# pmod_clock_961c7fa4.net
KiCad netlist of a schematic drawn in EAGLE
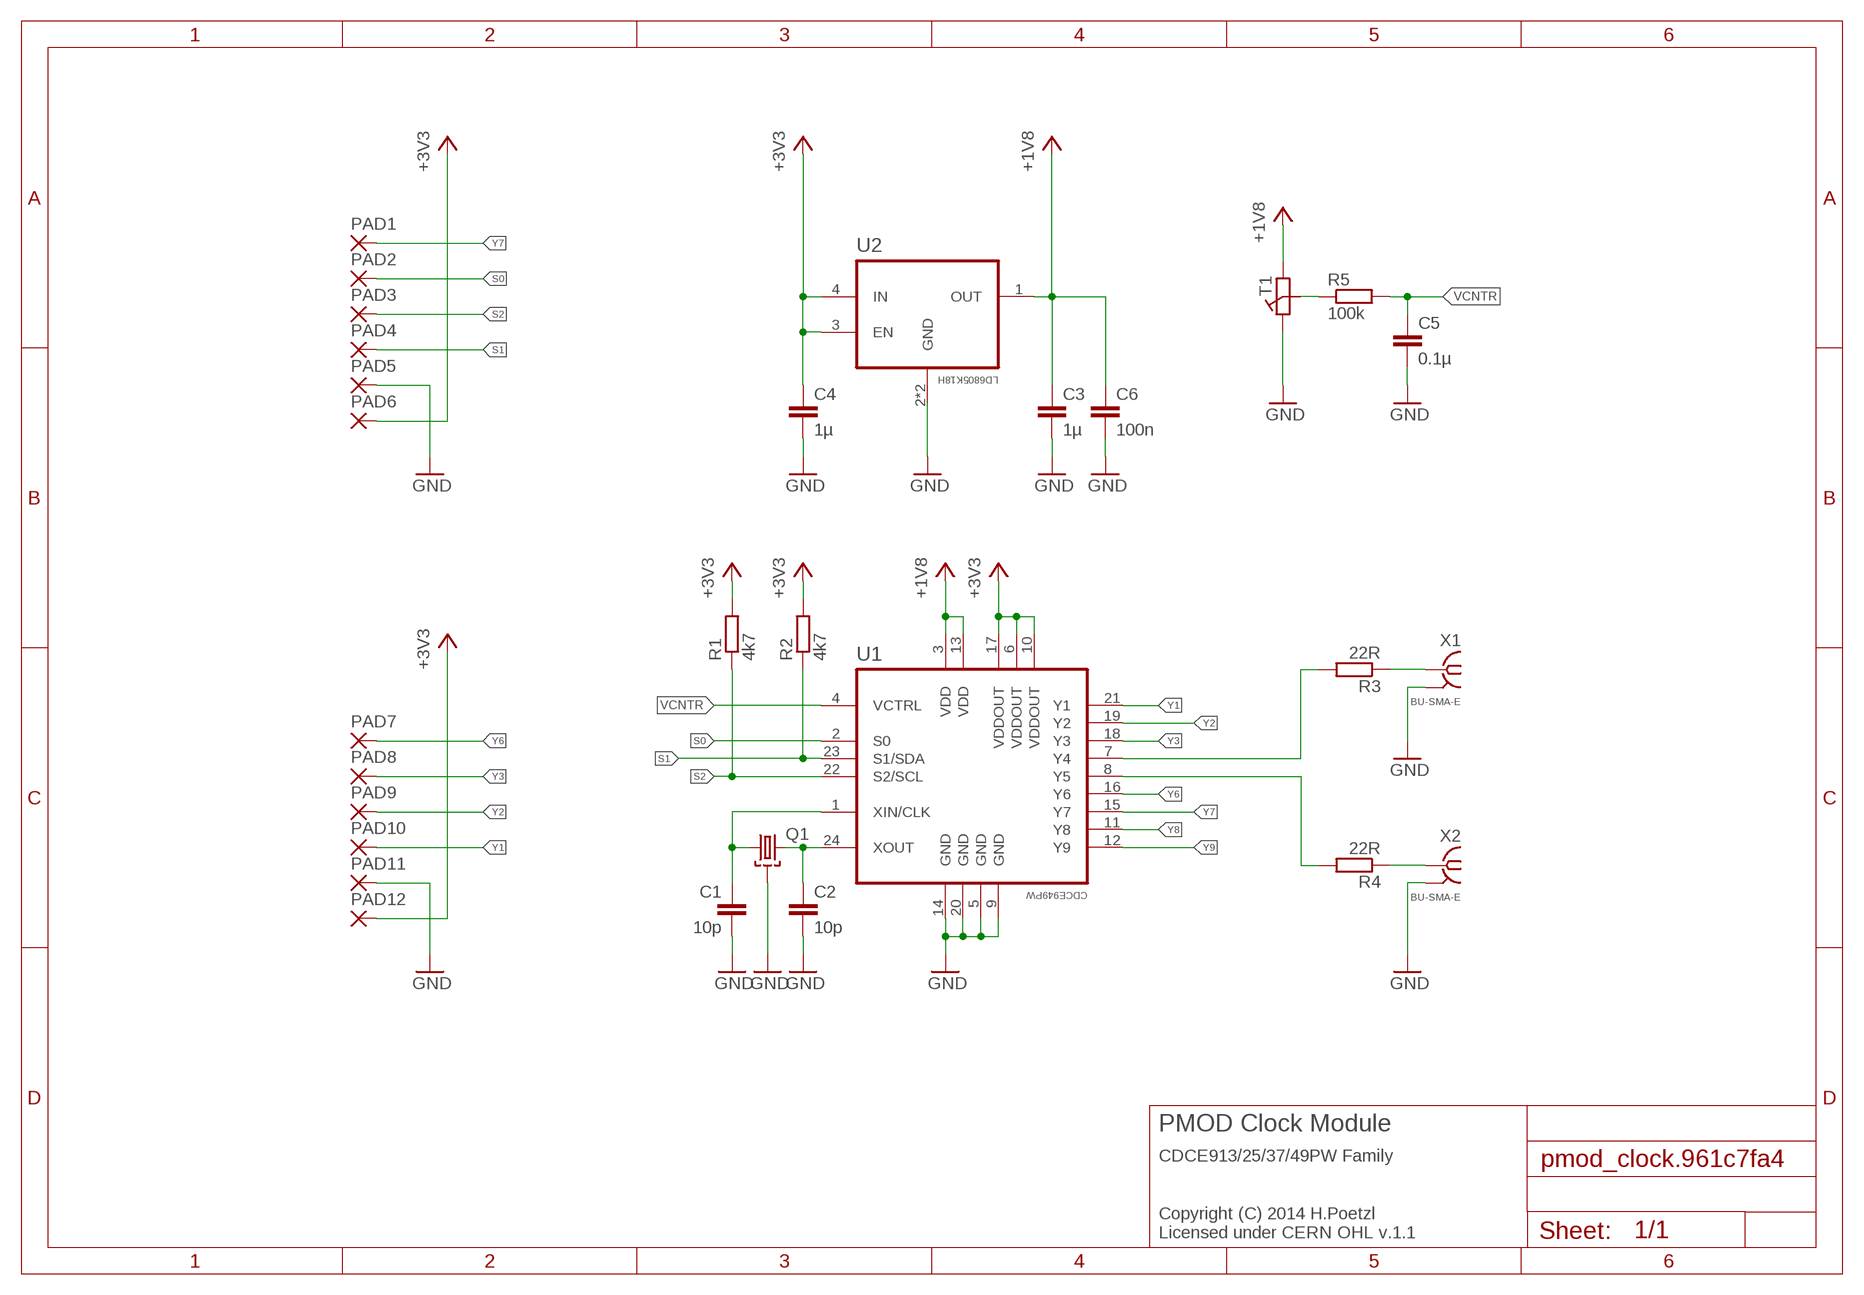
[diagram p0: schematic, sheet 1]

(export (version "E")
  (design (tool "Eeschema 10.0.6"))
  (components
    (comp (ref "C1")
      (value "10p")
      (footprint "eagle-import:C0402K")
      (libsource (lib "eagle-import") (part "C-EUC0402K"))
    )
    (comp (ref "C2")
      (value "10p")
      (footprint "eagle-import:C0402K")
      (libsource (lib "eagle-import") (part "C-EUC0402K"))
    )
    (comp (ref "C3")
      (value "1µ")
      (footprint "eagle-import:C0402")
      (libsource (lib "eagle-import") (part "C-EUC0402"))
    )
    (comp (ref "C4")
      (value "1µ")
      (footprint "eagle-import:C0402")
      (libsource (lib "eagle-import") (part "C-EUC0402"))
    )
    (comp (ref "C5")
      (value "0.1µ")
      (footprint "eagle-import:C0402")
      (libsource (lib "eagle-import") (part "C-EUC0402"))
    )
    (comp (ref "C6")
      (value "100n")
      (footprint "eagle-import:C0402")
      (libsource (lib "eagle-import") (part "C-EUC0402"))
    )
    (comp (ref "PAD1")
      (value "SMD2HR")
      (footprint "eagle-import:SMD1.27-3.175HR")
      (libsource (lib "eagle-import") (part "SMD2HR"))
    )
    (comp (ref "PAD2")
      (value "SMD2HR")
      (footprint "eagle-import:SMD1.27-3.175HR")
      (libsource (lib "eagle-import") (part "SMD2HR"))
    )
    (comp (ref "PAD3")
      (value "SMD2HR")
      (footprint "eagle-import:SMD1.27-3.175HR")
      (libsource (lib "eagle-import") (part "SMD2HR"))
    )
    (comp (ref "PAD4")
      (value "SMD2HR")
      (footprint "eagle-import:SMD1.27-3.175HR")
      (libsource (lib "eagle-import") (part "SMD2HR"))
    )
    (comp (ref "PAD5")
      (value "SMD2HR")
      (footprint "eagle-import:SMD1.27-3.175HR")
      (libsource (lib "eagle-import") (part "SMD2HR"))
    )
    (comp (ref "PAD6")
      (value "SMD2HR")
      (footprint "eagle-import:SMD1.27-3.175HR")
      (libsource (lib "eagle-import") (part "SMD2HR"))
    )
    (comp (ref "PAD7")
      (value "SMD2HR")
      (footprint "eagle-import:SMD1.27-3.175HR")
      (libsource (lib "eagle-import") (part "SMD2HR"))
    )
    (comp (ref "PAD8")
      (value "SMD2HR")
      (footprint "eagle-import:SMD1.27-3.175HR")
      (libsource (lib "eagle-import") (part "SMD2HR"))
    )
    (comp (ref "PAD9")
      (value "SMD2HR")
      (footprint "eagle-import:SMD1.27-3.175HR")
      (libsource (lib "eagle-import") (part "SMD2HR"))
    )
    (comp (ref "PAD10")
      (value "SMD2HR")
      (footprint "eagle-import:SMD1.27-3.175HR")
      (libsource (lib "eagle-import") (part "SMD2HR"))
    )
    (comp (ref "PAD11")
      (value "SMD2HR")
      (footprint "eagle-import:SMD1.27-3.175HR")
      (libsource (lib "eagle-import") (part "SMD2HR"))
    )
    (comp (ref "PAD12")
      (value "SMD2HR")
      (footprint "eagle-import:SMD1.27-3.175HR")
      (libsource (lib "eagle-import") (part "SMD2HR"))
    )
    (comp (ref "Q1")
      (value "SMD-4P-2G5.0X3.2+3.2X2.5")
      (footprint "eagle-import:MIX")
      (libsource (lib "eagle-import") (part "SMD-4P-2G5.0X3.2+3.2X2.5"))
    )
    (comp (ref "R1")
      (value "4k7")
      (footprint "eagle-import:R0402")
      (libsource (lib "eagle-import") (part "R-EU_R0402"))
    )
    (comp (ref "R2")
      (value "4k7")
      (footprint "eagle-import:R0402")
      (libsource (lib "eagle-import") (part "R-EU_R0402"))
    )
    (comp (ref "R3")
      (value "22R")
      (footprint "eagle-import:R0402")
      (libsource (lib "eagle-import") (part "R-EU_R0402"))
    )
    (comp (ref "R4")
      (value "22R")
      (footprint "eagle-import:R0402")
      (libsource (lib "eagle-import") (part "R-EU_R0402"))
    )
    (comp (ref "R5")
      (value "100k")
      (footprint "eagle-import:R0402")
      (libsource (lib "eagle-import") (part "R-EU_R0402"))
    )
    (comp (ref "T1")
      (value "PVZ2A")
      (footprint "eagle-import:TRIM-PVZ2A")
      (libsource (lib "eagle-import") (part "PVZ2A"))
    )
    (comp (ref "U1")
      (value "CDCE949PW")
      (footprint "eagle-import:SOP65P640X120-24N")
      (libsource (lib "eagle-import") (part "CDCE949PW"))
    )
    (comp (ref "U2")
      (value "LD6805K18H")
      (footprint "eagle-import:NXP_LD6805")
      (fields (field (name "MPN") "LD6805K/18H"))
      (libsource (lib "eagle-import") (part "LD6805K18H"))
    )
    (comp (ref "X1")
      (value "BU-SMA-E")
      (footprint "eagle-import:SMA-EDGE")
      (libsource (lib "eagle-import") (part "BU-SMA-E"))
    )
    (comp (ref "X2")
      (value "BU-SMA-E")
      (footprint "eagle-import:SMA-EDGE")
      (libsource (lib "eagle-import") (part "BU-SMA-E"))
    )
  )
  (nets
    (net (code "1") (name "+1V8") (class "Default")
      (node (ref "C3") (pin "1") (pinfunction "1_1") (pintype "passive"))
      (node (ref "C6") (pin "1") (pinfunction "1_1") (pintype "passive"))
      (node (ref "T1") (pin "1") (pinfunction "A_1") (pintype "bidirectional"))
      (node (ref "U1") (pin "13") (pinfunction "VDD_13") (pintype "power_in"))
      (node (ref "U1") (pin "3") (pinfunction "VDD_3") (pintype "power_in"))
      (node (ref "U2") (pin "1") (pinfunction "OUT_1") (pintype "power_in"))
    )
    (net (code "2") (name "+3V3") (class "Default")
      (node (ref "C4") (pin "1") (pinfunction "1_1") (pintype "passive"))
      (node (ref "PAD12") (pin "1") (pinfunction "P_1") (pintype "passive"))
      (node (ref "PAD6") (pin "1") (pinfunction "P_1") (pintype "passive"))
      (node (ref "R1") (pin "2") (pinfunction "2_2") (pintype "passive"))
      (node (ref "R2") (pin "2") (pinfunction "2_2") (pintype "passive"))
      (node (ref "U1") (pin "10") (pinfunction "VDDOUT_10") (pintype "power_in"))
      (node (ref "U1") (pin "17") (pinfunction "VDDOUT_17") (pintype "power_in"))
      (node (ref "U1") (pin "6") (pinfunction "VDDOUT_6") (pintype "power_in"))
      (node (ref "U2") (pin "3") (pinfunction "EN_3") (pintype "input"))
      (node (ref "U2") (pin "4") (pinfunction "IN_4") (pintype "power_in"))
    )
    (net (code "3") (name "GND") (class "Default")
      (node (ref "C1") (pin "2") (pinfunction "2_2") (pintype "passive"))
      (node (ref "C2") (pin "2") (pinfunction "2_2") (pintype "passive"))
      (node (ref "C3") (pin "2") (pinfunction "2_2") (pintype "passive"))
      (node (ref "C4") (pin "2") (pinfunction "2_2") (pintype "passive"))
      (node (ref "C5") (pin "2") (pinfunction "2_2") (pintype "passive"))
      (node (ref "C6") (pin "2") (pinfunction "2_2") (pintype "passive"))
      (node (ref "PAD11") (pin "1") (pinfunction "P_1") (pintype "passive"))
      (node (ref "PAD5") (pin "1") (pinfunction "P_1") (pintype "passive"))
      (node (ref "Q1") (pin "2") (pinfunction "GND_2") (pintype "power_in"))
      (node (ref "Q1") (pin "2@") (pinfunction "GND_2@") (pintype "power_in"))
      (node (ref "Q1") (pin "4") (pinfunction "GND_4") (pintype "power_in"))
      (node (ref "Q1") (pin "4@") (pinfunction "GND_4@") (pintype "power_in"))
      (node (ref "T1") (pin "3") (pinfunction "C_3") (pintype "bidirectional"))
      (node (ref "U1") (pin "14") (pinfunction "GND_14") (pintype "passive"))
      (node (ref "U1") (pin "20") (pinfunction "GND_20") (pintype "passive"))
      (node (ref "U1") (pin "5") (pinfunction "GND_5") (pintype "passive"))
      (node (ref "U1") (pin "9") (pinfunction "GND_9") (pintype "passive"))
      (node (ref "U2") (pin "2") (pinfunction "GND_2") (pintype "power_in"))
      (node (ref "U2") (pin "5") (pinfunction "GND_5") (pintype "power_in"))
      (node (ref "X1") (pin "2@3") (pinfunction "2_2@3") (pintype "passive"))
      (node (ref "X1") (pin "2@4") (pinfunction "2_2@4") (pintype "passive"))
      (node (ref "X2") (pin "2@3") (pinfunction "2_2@3") (pintype "passive"))
      (node (ref "X2") (pin "2@4") (pinfunction "2_2@4") (pintype "passive"))
    )
    (net (code "4") (name "Net-(R3-Pad1)") (class "Default")
      (node (ref "R3") (pin "1") (pinfunction "1_1") (pintype "passive"))
      (node (ref "X1") (pin "1") (pinfunction "1_1") (pintype "passive"))
    )
    (net (code "5") (name "Net-(R4-Pad1)") (class "Default")
      (node (ref "R4") (pin "1") (pinfunction "1_1") (pintype "passive"))
      (node (ref "X2") (pin "1") (pinfunction "1_1") (pintype "passive"))
    )
    (net (code "6") (name "Net-(T1-B)") (class "Default")
      (node (ref "R5") (pin "1") (pinfunction "1_1") (pintype "passive"))
      (node (ref "T1") (pin "2") (pinfunction "B_2") (pintype "bidirectional"))
    )
    (net (code "7") (name "Net-(U1-XIN{slash}CLK)") (class "Default")
      (node (ref "C1") (pin "1") (pinfunction "1_1") (pintype "passive"))
      (node (ref "Q1") (pin "1") (pinfunction "1_1") (pintype "passive"))
      (node (ref "Q1") (pin "1@") (pinfunction "1_1@") (pintype "passive"))
      (node (ref "U1") (pin "1") (pinfunction "XIN/CLK_1") (pintype "input"))
    )
    (net (code "8") (name "Net-(U1-XOUT)") (class "Default")
      (node (ref "C2") (pin "1") (pinfunction "1_1") (pintype "passive"))
      (node (ref "Q1") (pin "3") (pinfunction "2_3") (pintype "passive"))
      (node (ref "Q1") (pin "3@") (pinfunction "2_3@") (pintype "passive"))
      (node (ref "U1") (pin "24") (pinfunction "XOUT_24") (pintype "output"))
    )
    (net (code "9") (name "Net-(U1-Y4)") (class "Default")
      (node (ref "R3") (pin "2") (pinfunction "2_2") (pintype "passive"))
      (node (ref "U1") (pin "7") (pinfunction "Y4_7") (pintype "output"))
    )
    (net (code "10") (name "Net-(U1-Y5)") (class "Default")
      (node (ref "R4") (pin "2") (pinfunction "2_2") (pintype "passive"))
      (node (ref "U1") (pin "8") (pinfunction "Y5_8") (pintype "output"))
    )
    (net (code "11") (name "S0") (class "Default")
      (node (ref "PAD2") (pin "1") (pinfunction "P_1") (pintype "passive"))
      (node (ref "U1") (pin "2") (pinfunction "S0_2") (pintype "input"))
    )
    (net (code "12") (name "S1") (class "Default")
      (node (ref "PAD4") (pin "1") (pinfunction "P_1") (pintype "passive"))
      (node (ref "R2") (pin "1") (pinfunction "1_1") (pintype "passive"))
      (node (ref "U1") (pin "23") (pinfunction "S1/SDA_23") (pintype "bidirectional"))
    )
    (net (code "13") (name "S2") (class "Default")
      (node (ref "PAD3") (pin "1") (pinfunction "P_1") (pintype "passive"))
      (node (ref "R1") (pin "1") (pinfunction "1_1") (pintype "passive"))
      (node (ref "U1") (pin "22") (pinfunction "S2/SCL_22") (pintype "input"))
    )
    (net (code "14") (name "VCNTR") (class "Default")
      (node (ref "C5") (pin "1") (pinfunction "1_1") (pintype "passive"))
      (node (ref "R5") (pin "2") (pinfunction "2_2") (pintype "passive"))
      (node (ref "U1") (pin "4") (pinfunction "VCTRL_4") (pintype "input"))
    )
    (net (code "15") (name "Y1") (class "Default")
      (node (ref "PAD10") (pin "1") (pinfunction "P_1") (pintype "passive"))
      (node (ref "U1") (pin "21") (pinfunction "Y1_21") (pintype "output"))
    )
    (net (code "16") (name "Y2") (class "Default")
      (node (ref "PAD9") (pin "1") (pinfunction "P_1") (pintype "passive"))
      (node (ref "U1") (pin "19") (pinfunction "Y2_19") (pintype "output"))
    )
    (net (code "17") (name "Y3") (class "Default")
      (node (ref "PAD8") (pin "1") (pinfunction "P_1") (pintype "passive"))
      (node (ref "U1") (pin "18") (pinfunction "Y3_18") (pintype "output"))
    )
    (net (code "18") (name "Y6") (class "Default")
      (node (ref "PAD7") (pin "1") (pinfunction "P_1") (pintype "passive"))
      (node (ref "U1") (pin "16") (pinfunction "Y6_16") (pintype "output"))
    )
    (net (code "19") (name "Y7") (class "Default")
      (node (ref "PAD1") (pin "1") (pinfunction "P_1") (pintype "passive"))
      (node (ref "U1") (pin "15") (pinfunction "Y7_15") (pintype "output"))
    )
    (net (code "20") (name "Y8") (class "Default")
      (node (ref "U1") (pin "11") (pinfunction "Y8_11") (pintype "output"))
    )
    (net (code "21") (name "Y9") (class "Default")
      (node (ref "U1") (pin "12") (pinfunction "Y9_12") (pintype "output"))
    )
  )
)
